# MatrixSCH.net
KiCad netlist of a schematic drawn in Altium Designer
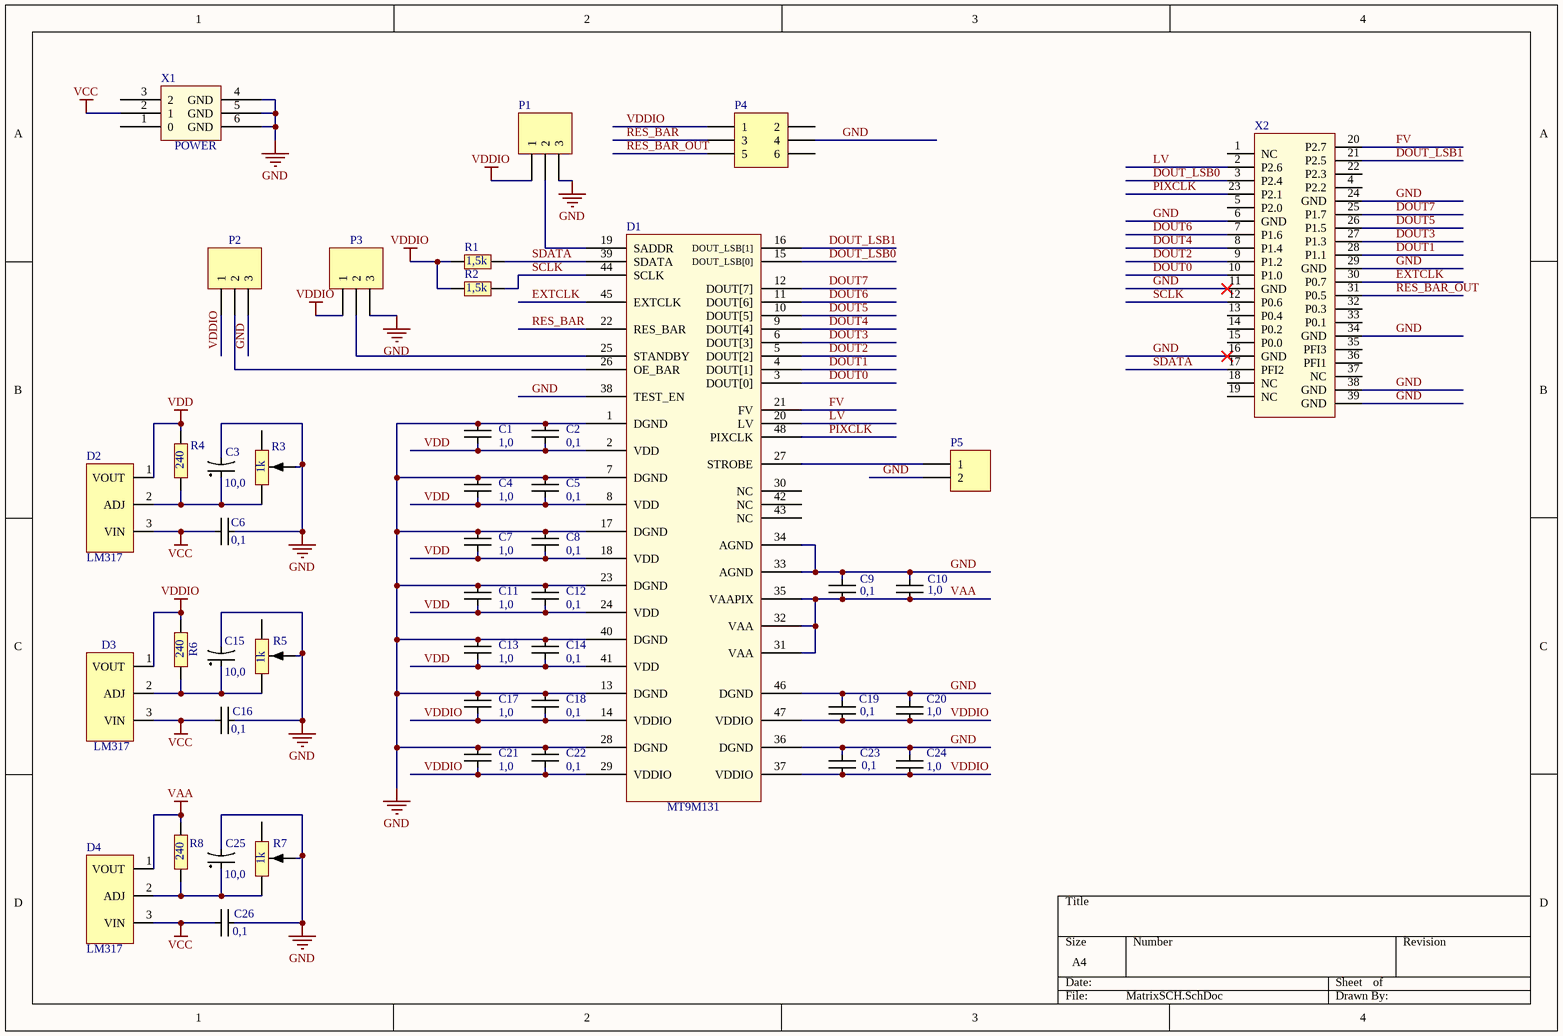
[diagram p0: MatrixSCH.SchDoc]

(export (version "E")
  (design (tool "Eeschema 10.0.6"))
  (components
    (comp (ref "C1")
      (value "1,0")
      (footprint "CAP_SMALL")
      (description "0805")
      (libsource (lib "Schlib") (part "CAP_SMALL"))
    )
    (comp (ref "C2")
      (value "0,1")
      (footprint "CAP_SMALL")
      (description "0805")
      (libsource (lib "Schlib") (part "CAP_SMALL"))
    )
    (comp (ref "C3")
      (value "10,0")
      (footprint "TYPE_C")
      (description "SMD")
      (libsource (lib "MIT_Schlib") (part "CAP_TANT"))
    )
    (comp (ref "C4")
      (value "1,0")
      (footprint "CAP_SMALL")
      (description "0805")
      (libsource (lib "Schlib") (part "CAP_SMALL"))
    )
    (comp (ref "C5")
      (value "0,1")
      (footprint "CAP_SMALL")
      (description "0805")
      (libsource (lib "Schlib") (part "CAP_SMALL"))
    )
    (comp (ref "C6")
      (value "0,1")
      (footprint "CAP_SMALL")
      (description "0805")
      (libsource (lib "Schlib") (part "CAP_SMALL"))
    )
    (comp (ref "C7")
      (value "1,0")
      (footprint "CAP_SMALL")
      (description "0805")
      (libsource (lib "Schlib") (part "CAP_SMALL"))
    )
    (comp (ref "C8")
      (value "0,1")
      (footprint "CAP_SMALL")
      (description "0805")
      (libsource (lib "Schlib") (part "CAP_SMALL"))
    )
    (comp (ref "C9")
      (value "0,1")
      (footprint "CAP_SMALL")
      (description "0805")
      (libsource (lib "Schlib") (part "CAP_SMALL"))
    )
    (comp (ref "C10")
      (value "1,0")
      (footprint "CAP_SMALL")
      (description "0805")
      (libsource (lib "Schlib") (part "CAP_SMALL"))
    )
    (comp (ref "C11")
      (value "1,0")
      (footprint "CAP_SMALL")
      (description "0805")
      (libsource (lib "Schlib") (part "CAP_SMALL"))
    )
    (comp (ref "C12")
      (value "0,1")
      (footprint "CAP_SMALL")
      (description "0805")
      (libsource (lib "Schlib") (part "CAP_SMALL"))
    )
    (comp (ref "C13")
      (value "1,0")
      (footprint "CAP_SMALL")
      (description "0805")
      (libsource (lib "Schlib") (part "CAP_SMALL"))
    )
    (comp (ref "C14")
      (value "0,1")
      (footprint "CAP_SMALL")
      (description "0805")
      (libsource (lib "Schlib") (part "CAP_SMALL"))
    )
    (comp (ref "C15")
      (value "10,0")
      (footprint "TYPE_C")
      (description "SMD")
      (libsource (lib "MIT_Schlib") (part "CAP_TANT"))
    )
    (comp (ref "C16")
      (value "0,1")
      (footprint "CAP_SMALL")
      (description "0805")
      (libsource (lib "Schlib") (part "CAP_SMALL"))
    )
    (comp (ref "C17")
      (value "1,0")
      (footprint "CAP_SMALL")
      (description "0805")
      (libsource (lib "Schlib") (part "CAP_SMALL"))
    )
    (comp (ref "C18")
      (value "0,1")
      (footprint "CAP_SMALL")
      (description "0805")
      (libsource (lib "Schlib") (part "CAP_SMALL"))
    )
    (comp (ref "C19")
      (value "0,1")
      (footprint "CAP_SMALL")
      (description "0805")
      (libsource (lib "Schlib") (part "CAP_SMALL"))
    )
    (comp (ref "C20")
      (value "1,0")
      (footprint "CAP_SMALL")
      (description "0805")
      (libsource (lib "Schlib") (part "CAP_SMALL"))
    )
    (comp (ref "C21")
      (value "1,0")
      (footprint "CAP_SMALL")
      (description "0805")
      (libsource (lib "Schlib") (part "CAP_SMALL"))
    )
    (comp (ref "C22")
      (value "0,1")
      (footprint "CAP_SMALL")
      (description "0805")
      (libsource (lib "Schlib") (part "CAP_SMALL"))
    )
    (comp (ref "C23")
      (value "0,1")
      (footprint "CAP_SMALL")
      (description "0805")
      (libsource (lib "Schlib") (part "CAP_SMALL"))
    )
    (comp (ref "C24")
      (value "1,0")
      (footprint "CAP_SMALL")
      (description "0805")
      (libsource (lib "Schlib") (part "CAP_SMALL"))
    )
    (comp (ref "C25")
      (value "10,0")
      (footprint "TYPE_C")
      (description "SMD")
      (libsource (lib "MIT_Schlib") (part "CAP_TANT"))
    )
    (comp (ref "C26")
      (value "0,1")
      (footprint "CAP_SMALL")
      (description "0805")
      (libsource (lib "Schlib") (part "CAP_SMALL"))
    )
    (comp (ref "D1")
      (value "MT9M131")
      (footprint "LCC48")
      (description "Matrix")
      (libsource (lib "MIT_Schlib") (part "MT9M131"))
    )
    (comp (ref "D2") (value "LM317") (footprint "D2PACK") (libsource (lib "MIT_Schlib") (part "LM317")))
    (comp (ref "D3") (value "LM317") (footprint "D2PACK") (libsource (lib "MIT_Schlib") (part "LM317")))
    (comp (ref "D4") (value "LM317") (footprint "D2PACK") (libsource (lib "MIT_Schlib") (part "LM317")))
    (comp (ref "P1")
      (value "Header 3")
      (footprint "HDR1X3")
      (description "Header, 3-Pin")
      (fields (field (name "PUBLISHER") "Altium Limited"))
      (libsource (lib "Miscellaneous Connectors") (part "Header 3"))
    )
    (comp (ref "P2")
      (value "Header 3")
      (footprint "HDR1X3")
      (description "Header, 3-Pin")
      (fields (field (name "PUBLISHER") "Altium Limited"))
      (libsource (lib "Miscellaneous Connectors") (part "Header 3"))
    )
    (comp (ref "P3")
      (value "Header 3")
      (footprint "HDR1X3")
      (description "Header, 3-Pin")
      (fields (field (name "PUBLISHER") "Altium Limited"))
      (libsource (lib "Miscellaneous Connectors") (part "Header 3"))
    )
    (comp (ref "P4")
      (value "Header 3X2")
      (footprint "HDR2X3")
      (description "Header, 3-Pin, Dual row")
      (fields (field (name "PUBLISHER") "Altium Limited"))
      (libsource (lib "Miscellaneous Connectors") (part "Header 3X2"))
    )
    (comp (ref "P5")
      (value "Header 2")
      (footprint "HDR1X2")
      (description "Header, 2-Pin")
      (fields (field (name "PUBLISHER") "Altium Limited"))
      (libsource (lib "Miscellaneous Connectors") (part "Header 2"))
    )
    (comp (ref "R1")
      (value "1,5k")
      (footprint "0805")
      (description "0805")
      (libsource (lib "") (part "RES0805_1"))
    )
    (comp (ref "R2")
      (value "1,5k")
      (footprint "0805")
      (description "0805")
      (libsource (lib "") (part "RES0805_1"))
    )
    (comp (ref "R3")
      (value "1k")
      (footprint "PV36W")
      (description "PV36W102C (СП5-2ВБ) 1 кОм")
      (libsource (lib "MIT_Schlib") (part "RES_VAR"))
    )
    (comp (ref "R4")
      (value "240")
      (footprint "0805")
      (description "0805")
      (libsource (lib "MIT_Schlib") (part "RES0805"))
    )
    (comp (ref "R5")
      (value "1k")
      (footprint "PV36W")
      (description "PV36W102C (СП5-2ВБ) 1 кОм")
      (libsource (lib "MIT_Schlib") (part "RES_VAR"))
    )
    (comp (ref "R6")
      (value "240")
      (footprint "0805")
      (description "0805")
      (libsource (lib "MIT_Schlib") (part "RES0805"))
    )
    (comp (ref "R7")
      (value "1k")
      (footprint "PV36W")
      (description "PV36W102C (СП5-2ВБ) 1 кОм")
      (libsource (lib "MIT_Schlib") (part "RES_VAR"))
    )
    (comp (ref "R8")
      (value "240")
      (footprint "0805")
      (description "0805")
      (libsource (lib "MIT_Schlib") (part "RES0805"))
    )
    (comp (ref "X1") (value "POWER") (footprint "POWER") (libsource (lib "Schlib") (part "POWER")))
    (comp (ref "X2")
      (value "D-SUB_FEMALE")
      (footprint "CHEAP_CONN_FEMALE")
      (libsource (lib "Schlib") (part "CHEAP_CON_37_FEMALE"))
    )
  )
  (nets
    (net (code "1") (name "/DOUT0") (class "Default")
      (node (ref "D1") (pin "3") (pinfunction "DOUT[0]_3") (pintype "passive"))
      (node (ref "X2") (pin "10") (pinfunction "P1.0_10") (pintype "passive"))
    )
    (net (code "2") (name "/DOUT1") (class "Default")
      (node (ref "D1") (pin "4") (pinfunction "DOUT[1]_4") (pintype "passive"))
      (node (ref "X2") (pin "28") (pinfunction "P1.1_28") (pintype "passive"))
    )
    (net (code "3") (name "/DOUT2") (class "Default")
      (node (ref "D1") (pin "5") (pinfunction "DOUT[2]_5") (pintype "passive"))
      (node (ref "X2") (pin "9") (pinfunction "P1.2_9") (pintype "passive"))
    )
    (net (code "4") (name "/DOUT3") (class "Default")
      (node (ref "D1") (pin "6") (pinfunction "DOUT[3]_6") (pintype "passive"))
      (node (ref "X2") (pin "27") (pinfunction "P1.3_27") (pintype "passive"))
    )
    (net (code "5") (name "/DOUT4") (class "Default")
      (node (ref "D1") (pin "9") (pinfunction "DOUT[4]_9") (pintype "passive"))
      (node (ref "X2") (pin "8") (pinfunction "P1.4_8") (pintype "passive"))
    )
    (net (code "6") (name "/DOUT5") (class "Default")
      (node (ref "D1") (pin "10") (pinfunction "DOUT[5]_10") (pintype "passive"))
      (node (ref "X2") (pin "26") (pinfunction "P1.5_26") (pintype "passive"))
    )
    (net (code "7") (name "/DOUT6") (class "Default")
      (node (ref "D1") (pin "11") (pinfunction "DOUT[6]_11") (pintype "passive"))
      (node (ref "X2") (pin "7") (pinfunction "P1.6_7") (pintype "passive"))
    )
    (net (code "8") (name "/DOUT7") (class "Default")
      (node (ref "D1") (pin "12") (pinfunction "DOUT[7]_12") (pintype "passive"))
      (node (ref "X2") (pin "25") (pinfunction "P1.7_25") (pintype "passive"))
    )
    (net (code "9") (name "/DOUT_LSB0") (class "Default")
      (node (ref "D1") (pin "15") (pinfunction "DOUT_LSB[0]_15") (pintype "passive"))
      (node (ref "X2") (pin "3") (pinfunction "P2.4_3") (pintype "passive"))
    )
    (net (code "10") (name "/DOUT_LSB1") (class "Default")
      (node (ref "D1") (pin "16") (pinfunction "DOUT_LSB[1]_16") (pintype "passive"))
      (node (ref "X2") (pin "21") (pinfunction "P2.5_21") (pintype "passive"))
    )
    (net (code "11") (name "/EXTCLK") (class "Default")
      (node (ref "D1") (pin "45") (pinfunction "EXTCLK_45") (pintype "passive"))
      (node (ref "X2") (pin "30") (pinfunction "P0.7_30") (pintype "passive"))
    )
    (net (code "12") (name "/FV") (class "Default")
      (node (ref "D1") (pin "21") (pinfunction "FV_21") (pintype "passive"))
      (node (ref "X2") (pin "20") (pinfunction "P2.7_20") (pintype "passive"))
    )
    (net (code "13") (name "/LV") (class "Default")
      (node (ref "D1") (pin "20") (pinfunction "LV_20") (pintype "passive"))
      (node (ref "X2") (pin "2") (pinfunction "P2.6_2") (pintype "passive"))
    )
    (net (code "14") (name "/PIXCLK") (class "Default")
      (node (ref "D1") (pin "48") (pinfunction "PIXCLK_48") (pintype "passive"))
      (node (ref "X2") (pin "23") (pinfunction "P2.1_23") (pintype "passive"))
    )
    (net (code "15") (name "/RES_BAR") (class "Default")
      (node (ref "D1") (pin "22") (pinfunction "RES_BAR_22") (pintype "passive"))
      (node (ref "P4") (pin "3") (pinfunction "3_3") (pintype "passive"))
    )
    (net (code "16") (name "/RES_BAR_OUT") (class "Default")
      (node (ref "P4") (pin "5") (pinfunction "5_5") (pintype "passive"))
      (node (ref "X2") (pin "31") (pinfunction "P0.5_31") (pintype "passive"))
    )
    (net (code "17") (name "/SCLK") (class "Default")
      (node (ref "D1") (pin "44") (pinfunction "SCLK_44") (pintype "passive"))
      (node (ref "R2") (pin "2") (pinfunction "2_2") (pintype "passive"))
      (node (ref "X2") (pin "12") (pinfunction "P0.6_12") (pintype "passive"))
    )
    (net (code "18") (name "/SDATA") (class "Default")
      (node (ref "D1") (pin "39") (pinfunction "SDATA_39") (pintype "passive"))
      (node (ref "R1") (pin "2") (pinfunction "2_2") (pintype "passive"))
      (node (ref "X2") (pin "17") (pinfunction "PFI2_17") (pintype "passive"))
    )
    (net (code "19") (name "GND") (class "Default")
      (node (ref "C1") (pin "1") (pinfunction "1_1") (pintype "passive"))
      (node (ref "C10") (pin "2") (pinfunction "2_2") (pintype "passive"))
      (node (ref "C11") (pin "1") (pinfunction "1_1") (pintype "passive"))
      (node (ref "C12") (pin "1") (pinfunction "1_1") (pintype "passive"))
      (node (ref "C13") (pin "1") (pinfunction "1_1") (pintype "passive"))
      (node (ref "C14") (pin "1") (pinfunction "1_1") (pintype "passive"))
      (node (ref "C15") (pin "1") (pinfunction "1_1") (pintype "passive"))
      (node (ref "C16") (pin "2") (pinfunction "2_2") (pintype "passive"))
      (node (ref "C17") (pin "1") (pinfunction "1_1") (pintype "passive"))
      (node (ref "C18") (pin "1") (pinfunction "1_1") (pintype "passive"))
      (node (ref "C19") (pin "2") (pinfunction "2_2") (pintype "passive"))
      (node (ref "C2") (pin "1") (pinfunction "1_1") (pintype "passive"))
      (node (ref "C20") (pin "2") (pinfunction "2_2") (pintype "passive"))
      (node (ref "C21") (pin "1") (pinfunction "1_1") (pintype "passive"))
      (node (ref "C22") (pin "1") (pinfunction "1_1") (pintype "passive"))
      (node (ref "C23") (pin "2") (pinfunction "2_2") (pintype "passive"))
      (node (ref "C24") (pin "2") (pinfunction "2_2") (pintype "passive"))
      (node (ref "C25") (pin "1") (pinfunction "1_1") (pintype "passive"))
      (node (ref "C26") (pin "2") (pinfunction "2_2") (pintype "passive"))
      (node (ref "C3") (pin "1") (pinfunction "1_1") (pintype "passive"))
      (node (ref "C4") (pin "1") (pinfunction "1_1") (pintype "passive"))
      (node (ref "C5") (pin "1") (pinfunction "1_1") (pintype "passive"))
      (node (ref "C6") (pin "2") (pinfunction "2_2") (pintype "passive"))
      (node (ref "C7") (pin "1") (pinfunction "1_1") (pintype "passive"))
      (node (ref "C8") (pin "1") (pinfunction "1_1") (pintype "passive"))
      (node (ref "C9") (pin "2") (pinfunction "2_2") (pintype "passive"))
      (node (ref "D1") (pin "1") (pinfunction "DGND_1") (pintype "passive"))
      (node (ref "D1") (pin "13") (pinfunction "DGND_13") (pintype "passive"))
      (node (ref "D1") (pin "17") (pinfunction "DGND_17") (pintype "passive"))
      (node (ref "D1") (pin "23") (pinfunction "DGND_23") (pintype "passive"))
      (node (ref "D1") (pin "28") (pinfunction "DGND_28") (pintype "passive"))
      (node (ref "D1") (pin "33") (pinfunction "AGND_33") (pintype "passive"))
      (node (ref "D1") (pin "34") (pinfunction "AGND_34") (pintype "passive"))
      (node (ref "D1") (pin "36") (pinfunction "DGND_36") (pintype "passive"))
      (node (ref "D1") (pin "38") (pinfunction "TEST_EN_38") (pintype "passive"))
      (node (ref "D1") (pin "40") (pinfunction "DGND_40") (pintype "passive"))
      (node (ref "D1") (pin "46") (pinfunction "DGND_46") (pintype "passive"))
      (node (ref "D1") (pin "7") (pinfunction "DGND_7") (pintype "passive"))
      (node (ref "P1") (pin "3") (pinfunction "3_3") (pintype "passive"))
      (node (ref "P2") (pin "3") (pinfunction "3_3") (pintype "passive"))
      (node (ref "P3") (pin "3") (pinfunction "3_3") (pintype "passive"))
      (node (ref "P4") (pin "4") (pinfunction "4_4") (pintype "passive"))
      (node (ref "P5") (pin "2") (pinfunction "2_2") (pintype "passive"))
      (node (ref "R3") (pin "2") (pinfunction "2_2") (pintype "passive"))
      (node (ref "R5") (pin "2") (pinfunction "2_2") (pintype "passive"))
      (node (ref "R7") (pin "2") (pinfunction "2_2") (pintype "passive"))
      (node (ref "X1") (pin "4") (pinfunction "GND_4") (pintype "passive"))
      (node (ref "X1") (pin "5") (pinfunction "GND_5") (pintype "passive"))
      (node (ref "X1") (pin "6") (pinfunction "GND_6") (pintype "passive"))
      (node (ref "X2") (pin "11") (pinfunction "GND_11") (pintype "passive"))
      (node (ref "X2") (pin "16") (pinfunction "GND_16") (pintype "passive"))
      (node (ref "X2") (pin "24") (pinfunction "GND_24") (pintype "passive"))
      (node (ref "X2") (pin "29") (pinfunction "GND_29") (pintype "passive"))
      (node (ref "X2") (pin "34") (pinfunction "GND_34") (pintype "passive"))
      (node (ref "X2") (pin "38") (pinfunction "GND_38") (pintype "passive"))
      (node (ref "X2") (pin "39") (pinfunction "GND_39") (pintype "passive"))
      (node (ref "X2") (pin "6") (pinfunction "GND_6") (pintype "passive"))
    )
    (net (code "20") (name "Net-(D1-OE_BAR)") (class "Default")
      (node (ref "D1") (pin "26") (pinfunction "OE_BAR_26") (pintype "passive"))
      (node (ref "P2") (pin "2") (pinfunction "2_2") (pintype "passive"))
    )
    (net (code "21") (name "Net-(D1-SADDR)") (class "Default")
      (node (ref "D1") (pin "19") (pinfunction "SADDR_19") (pintype "passive"))
      (node (ref "P1") (pin "2") (pinfunction "2_2") (pintype "passive"))
    )
    (net (code "22") (name "Net-(D1-STANDBY)") (class "Default")
      (node (ref "D1") (pin "25") (pinfunction "STANDBY_25") (pintype "passive"))
      (node (ref "P3") (pin "2") (pinfunction "2_2") (pintype "passive"))
    )
    (net (code "23") (name "Net-(D1-STROBE)") (class "Default")
      (node (ref "D1") (pin "27") (pinfunction "STROBE_27") (pintype "passive"))
      (node (ref "P5") (pin "1") (pinfunction "1_1") (pintype "passive"))
    )
    (net (code "24") (name "Net-(D2-ADJ)") (class "Default")
      (node (ref "C3") (pin "2") (pinfunction "2_2") (pintype "passive"))
      (node (ref "D2") (pin "2") (pinfunction "ADJ_2") (pintype "passive"))
      (node (ref "R3") (pin "1") (pinfunction "1_1") (pintype "passive"))
      (node (ref "R4") (pin "2") (pinfunction "2_2") (pintype "passive"))
    )
    (net (code "25") (name "Net-(D3-ADJ)") (class "Default")
      (node (ref "C15") (pin "2") (pinfunction "2_2") (pintype "passive"))
      (node (ref "D3") (pin "2") (pinfunction "ADJ_2") (pintype "passive"))
      (node (ref "R5") (pin "1") (pinfunction "1_1") (pintype "passive"))
      (node (ref "R6") (pin "2") (pinfunction "2_2") (pintype "passive"))
    )
    (net (code "26") (name "Net-(D4-ADJ)") (class "Default")
      (node (ref "C25") (pin "2") (pinfunction "2_2") (pintype "passive"))
      (node (ref "D4") (pin "2") (pinfunction "ADJ_2") (pintype "passive"))
      (node (ref "R7") (pin "1") (pinfunction "1_1") (pintype "passive"))
      (node (ref "R8") (pin "2") (pinfunction "2_2") (pintype "passive"))
    )
    (net (code "27") (name "VAA") (class "Default")
      (node (ref "C10") (pin "1") (pinfunction "1_1") (pintype "passive"))
      (node (ref "C9") (pin "1") (pinfunction "1_1") (pintype "passive"))
      (node (ref "D1") (pin "31") (pinfunction "VAA_31") (pintype "passive"))
      (node (ref "D1") (pin "32") (pinfunction "VAA_32") (pintype "passive"))
      (node (ref "D1") (pin "35") (pinfunction "VAAPIX_35") (pintype "passive"))
      (node (ref "D4") (pin "1") (pinfunction "VOUT_1") (pintype "passive"))
      (node (ref "R8") (pin "1") (pinfunction "1_1") (pintype "passive"))
    )
    (net (code "28") (name "VCC") (class "Default")
      (node (ref "C16") (pin "1") (pinfunction "1_1") (pintype "passive"))
      (node (ref "C26") (pin "1") (pinfunction "1_1") (pintype "passive"))
      (node (ref "C6") (pin "1") (pinfunction "1_1") (pintype "passive"))
      (node (ref "D2") (pin "3") (pinfunction "VIN_3") (pintype "passive"))
      (node (ref "D3") (pin "3") (pinfunction "VIN_3") (pintype "passive"))
      (node (ref "D4") (pin "3") (pinfunction "VIN_3") (pintype "passive"))
      (node (ref "X1") (pin "2") (pinfunction "1_2") (pintype "passive"))
    )
    (net (code "29") (name "VDD") (class "Default")
      (node (ref "C1") (pin "2") (pinfunction "2_2") (pintype "passive"))
      (node (ref "C11") (pin "2") (pinfunction "2_2") (pintype "passive"))
      (node (ref "C12") (pin "2") (pinfunction "2_2") (pintype "passive"))
      (node (ref "C13") (pin "2") (pinfunction "2_2") (pintype "passive"))
      (node (ref "C14") (pin "2") (pinfunction "2_2") (pintype "passive"))
      (node (ref "C2") (pin "2") (pinfunction "2_2") (pintype "passive"))
      (node (ref "C4") (pin "2") (pinfunction "2_2") (pintype "passive"))
      (node (ref "C5") (pin "2") (pinfunction "2_2") (pintype "passive"))
      (node (ref "C7") (pin "2") (pinfunction "2_2") (pintype "passive"))
      (node (ref "C8") (pin "2") (pinfunction "2_2") (pintype "passive"))
      (node (ref "D1") (pin "18") (pinfunction "VDD_18") (pintype "passive"))
      (node (ref "D1") (pin "2") (pinfunction "VDD_2") (pintype "passive"))
      (node (ref "D1") (pin "24") (pinfunction "VDD_24") (pintype "passive"))
      (node (ref "D1") (pin "41") (pinfunction "VDD_41") (pintype "passive"))
      (node (ref "D1") (pin "8") (pinfunction "VDD_8") (pintype "passive"))
      (node (ref "D2") (pin "1") (pinfunction "VOUT_1") (pintype "passive"))
      (node (ref "R4") (pin "1") (pinfunction "1_1") (pintype "passive"))
    )
    (net (code "30") (name "VDDIO") (class "Default")
      (node (ref "C17") (pin "2") (pinfunction "2_2") (pintype "passive"))
      (node (ref "C18") (pin "2") (pinfunction "2_2") (pintype "passive"))
      (node (ref "C19") (pin "1") (pinfunction "1_1") (pintype "passive"))
      (node (ref "C20") (pin "1") (pinfunction "1_1") (pintype "passive"))
      (node (ref "C21") (pin "2") (pinfunction "2_2") (pintype "passive"))
      (node (ref "C22") (pin "2") (pinfunction "2_2") (pintype "passive"))
      (node (ref "C23") (pin "1") (pinfunction "1_1") (pintype "passive"))
      (node (ref "C24") (pin "1") (pinfunction "1_1") (pintype "passive"))
      (node (ref "D1") (pin "14") (pinfunction "VDDIO_14") (pintype "passive"))
      (node (ref "D1") (pin "29") (pinfunction "VDDIO_29") (pintype "passive"))
      (node (ref "D1") (pin "37") (pinfunction "VDDIO_37") (pintype "passive"))
      (node (ref "D1") (pin "47") (pinfunction "VDDIO_47") (pintype "passive"))
      (node (ref "D3") (pin "1") (pinfunction "VOUT_1") (pintype "passive"))
      (node (ref "P1") (pin "1") (pinfunction "1_1") (pintype "passive"))
      (node (ref "P2") (pin "1") (pinfunction "1_1") (pintype "passive"))
      (node (ref "P3") (pin "1") (pinfunction "1_1") (pintype "passive"))
      (node (ref "P4") (pin "1") (pinfunction "1_1") (pintype "passive"))
      (node (ref "R1") (pin "1") (pinfunction "1_1") (pintype "passive"))
      (node (ref "R2") (pin "1") (pinfunction "1_1") (pintype "passive"))
      (node (ref "R6") (pin "1") (pinfunction "1_1") (pintype "passive"))
    )
    (net (code "31") (name "unconnected-(D1-NC-Pad30)") (class "Default")
      (node (ref "D1") (pin "30") (pinfunction "NC_30") (pintype "passive"))
    )
    (net (code "32") (name "unconnected-(D1-NC-Pad42)") (class "Default")
      (node (ref "D1") (pin "42") (pinfunction "NC_42") (pintype "passive"))
    )
    (net (code "33") (name "unconnected-(D1-NC-Pad43)") (class "Default")
      (node (ref "D1") (pin "43") (pinfunction "NC_43") (pintype "passive"))
    )
    (net (code "34") (name "unconnected-(P4-Pad2)") (class "Default")
      (node (ref "P4") (pin "2") (pinfunction "2_2") (pintype "passive"))
    )
    (net (code "35") (name "unconnected-(P4-Pad6)") (class "Default")
      (node (ref "P4") (pin "6") (pinfunction "6_6") (pintype "passive"))
    )
    (net (code "36") (name "unconnected-(R3-Pad3)") (class "Default")
      (node (ref "R3") (pin "3") (pinfunction "3_3") (pintype "passive"))
    )
    (net (code "37") (name "unconnected-(R5-Pad3)") (class "Default")
      (node (ref "R5") (pin "3") (pinfunction "3_3") (pintype "passive"))
    )
    (net (code "38") (name "unconnected-(R7-Pad3)") (class "Default")
      (node (ref "R7") (pin "3") (pinfunction "3_3") (pintype "passive"))
    )
    (net (code "39") (name "unconnected-(X1-0-Pad1)") (class "Default")
      (node (ref "X1") (pin "1") (pinfunction "0_1") (pintype "passive"))
    )
    (net (code "40") (name "unconnected-(X1-2-Pad3)") (class "Default")
      (node (ref "X1") (pin "3") (pinfunction "2_3") (pintype "passive"))
    )
    (net (code "41") (name "unconnected-(X2-NC-Pad1)") (class "Default")
      (node (ref "X2") (pin "1") (pinfunction "NC_1") (pintype "passive"))
    )
    (net (code "42") (name "unconnected-(X2-NC-Pad18)") (class "Default")
      (node (ref "X2") (pin "18") (pinfunction "NC_18") (pintype "passive"))
    )
    (net (code "43") (name "unconnected-(X2-NC-Pad19)") (class "Default")
      (node (ref "X2") (pin "19") (pinfunction "NC_19") (pintype "passive"))
    )
    (net (code "44") (name "unconnected-(X2-NC-Pad37)") (class "Default")
      (node (ref "X2") (pin "37") (pinfunction "NC_37") (pintype "passive"))
    )
    (net (code "45") (name "unconnected-(X2-P0.0-Pad15)") (class "Default")
      (node (ref "X2") (pin "15") (pinfunction "P0.0_15") (pintype "passive"))
    )
    (net (code "46") (name "unconnected-(X2-P0.1-Pad33)") (class "Default")
      (node (ref "X2") (pin "33") (pinfunction "P0.1_33") (pintype "passive"))
    )
    (net (code "47") (name "unconnected-(X2-P0.2-Pad14)") (class "Default")
      (node (ref "X2") (pin "14") (pinfunction "P0.2_14") (pintype "passive"))
    )
    (net (code "48") (name "unconnected-(X2-P0.3-Pad32)") (class "Default")
      (node (ref "X2") (pin "32") (pinfunction "P0.3_32") (pintype "passive"))
    )
    (net (code "49") (name "unconnected-(X2-P0.4-Pad13)") (class "Default")
      (node (ref "X2") (pin "13") (pinfunction "P0.4_13") (pintype "passive"))
    )
    (net (code "50") (name "unconnected-(X2-P2.0-Pad5)") (class "Default")
      (node (ref "X2") (pin "5") (pinfunction "P2.0_5") (pintype "passive"))
    )
    (net (code "51") (name "unconnected-(X2-P2.2-Pad4)") (class "Default")
      (node (ref "X2") (pin "4") (pinfunction "P2.2_4") (pintype "passive"))
    )
    (net (code "52") (name "unconnected-(X2-P2.3-Pad22)") (class "Default")
      (node (ref "X2") (pin "22") (pinfunction "P2.3_22") (pintype "passive"))
    )
    (net (code "53") (name "unconnected-(X2-PFI1-Pad36)") (class "Default")
      (node (ref "X2") (pin "36") (pinfunction "PFI1_36") (pintype "passive"))
    )
    (net (code "54") (name "unconnected-(X2-PFI3-Pad35)") (class "Default")
      (node (ref "X2") (pin "35") (pinfunction "PFI3_35") (pintype "passive"))
    )
  )
)
